# Remote.net
KiCad netlist of a schematic drawn in EAGLE
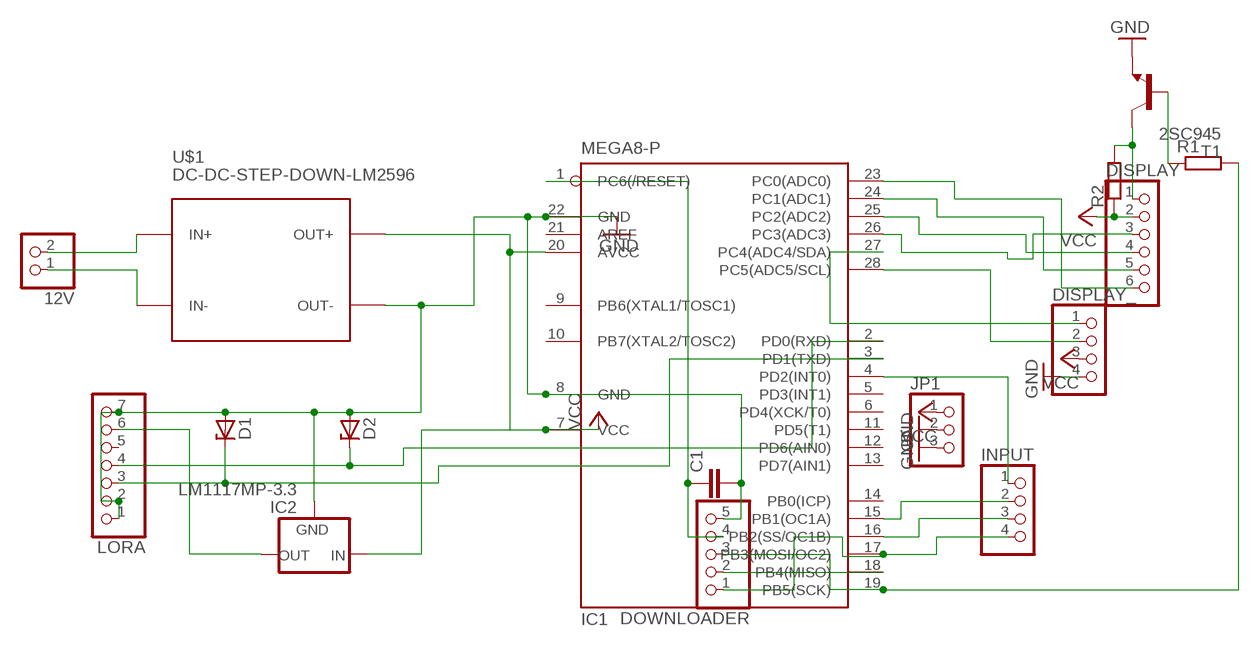
[diagram p0: schematic, sheet 1]

(export (version "E")
  (design (tool "Eeschema 10.0.6"))
  (components
    (comp (ref "12V")
      (value "PINHD-1X2")
      (footprint "eagle-import:1X02")
      (libsource (lib "eagle-import") (part "PINHD-1X2"))
    )
    (comp (ref "C1")
      (value "C-EU025-024X044")
      (footprint "eagle-import:C025-024X044")
      (libsource (lib "eagle-import") (part "C-EU025-024X044"))
    )
    (comp (ref "D1")
      (value "ZENER-DIODEDO35Z10")
      (footprint "eagle-import:DO35Z10")
      (libsource (lib "eagle-import") (part "ZENER-DIODEDO35Z10"))
    )
    (comp (ref "D2")
      (value "ZENER-DIODEDO35Z10")
      (footprint "eagle-import:DO35Z10")
      (libsource (lib "eagle-import") (part "ZENER-DIODEDO35Z10"))
    )
    (comp (ref "DISPLAY")
      (value "PINHD-1X6")
      (footprint "eagle-import:1X06")
      (libsource (lib "eagle-import") (part "PINHD-1X6"))
    )
    (comp (ref "DISPLAY_")
      (value "PINHD-1X4")
      (footprint "eagle-import:1X04")
      (libsource (lib "eagle-import") (part "PINHD-1X4"))
    )
    (comp (ref "DOWNLOADER")
      (value "PINHD-1X5")
      (footprint "eagle-import:1X05")
      (libsource (lib "eagle-import") (part "PINHD-1X5"))
    )
    (comp (ref "IC1")
      (value "MEGA8-P")
      (footprint "eagle-import:DIL28-3")
      (libsource (lib "eagle-import") (part "MEGA8-P"))
    )
    (comp (ref "IC2")
      (value "LM1117MP-3.3")
      (footprint "eagle-import:SOT223")
      (fields (field (name "MF") "Texas Instruments"))
      (libsource (lib "eagle-import") (part "LM1117?-MP3.3"))
    )
    (comp (ref "INPUT")
      (value "PINHD-1X4")
      (footprint "eagle-import:1X04")
      (libsource (lib "eagle-import") (part "PINHD-1X4"))
    )
    (comp (ref "JP1")
      (value "PINHD-1X3")
      (footprint "eagle-import:1X03")
      (libsource (lib "eagle-import") (part "PINHD-1X3"))
    )
    (comp (ref "LORA")
      (value "PINHD-1X7")
      (footprint "eagle-import:1X07")
      (libsource (lib "eagle-import") (part "PINHD-1X7"))
    )
    (comp (ref "R1")
      (value "R-EU_0204/7")
      (footprint "eagle-import:0204_7")
      (libsource (lib "eagle-import") (part "R-EU_0204/7"))
    )
    (comp (ref "R2")
      (value "R-EU_0204/7")
      (footprint "eagle-import:0204_7")
      (libsource (lib "eagle-import") (part "R-EU_0204/7"))
    )
    (comp (ref "T1")
      (value "2SC945")
      (footprint "eagle-import:TO92-ECB")
      (libsource (lib "eagle-import") (part "2SC945"))
    )
    (comp (ref "U$1")
      (value "DC-DC-STEP-DOWN-LM2596")
      (footprint "eagle-import:DC-DC-STEP-DOWN-LM2596")
      (libsource (lib "eagle-import") (part "DC-DC-STEP-DOWN-LM2596"))
    )
  )
  (nets
    (net (code "1") (name "GND") (class "Default")
      (node (ref "C1") (pin "2") (pinfunction "2_2") (pintype "passive"))
      (node (ref "D1") (pin "A") (pinfunction "A_A") (pintype "passive"))
      (node (ref "D2") (pin "A") (pinfunction "A_A") (pintype "passive"))
      (node (ref "DISPLAY_") (pin "4") (pinfunction "4_4") (pintype "passive"))
      (node (ref "DOWNLOADER") (pin "5") (pinfunction "5_5") (pintype "passive"))
      (node (ref "IC1") (pin "22") (pinfunction "GND_22") (pintype "power_in"))
      (node (ref "IC1") (pin "8") (pinfunction "GND_8") (pintype "power_in"))
      (node (ref "IC2") (pin "1") (pinfunction "GND_1") (pintype "input"))
      (node (ref "JP1") (pin "2") (pinfunction "2_2") (pintype "passive"))
      (node (ref "JP1") (pin "3") (pinfunction "3_3") (pintype "passive"))
      (node (ref "LORA") (pin "1") (pinfunction "1_1") (pintype "passive"))
      (node (ref "LORA") (pin "2") (pinfunction "2_2") (pintype "passive"))
      (node (ref "LORA") (pin "7") (pinfunction "7_7") (pintype "passive"))
      (node (ref "T1") (pin "E") (pinfunction "E_E") (pintype "passive"))
      (node (ref "U$1") (pin "OUT-") (pinfunction "OUT-_OUT-") (pintype "bidirectional"))
    )
    (net (code "2") (name "Net-(12V-Pad1)") (class "Default")
      (node (ref "12V") (pin "1") (pinfunction "1_1") (pintype "passive"))
      (node (ref "U$1") (pin "IN-") (pinfunction "IN-_IN-") (pintype "bidirectional"))
    )
    (net (code "3") (name "Net-(12V-Pad2)") (class "Default")
      (node (ref "12V") (pin "2") (pinfunction "2_2") (pintype "passive"))
      (node (ref "U$1") (pin "IN+") (pinfunction "IN+_IN+") (pintype "bidirectional"))
    )
    (net (code "4") (name "Net-(DISPLAY-Pad1)") (class "Default")
      (node (ref "DISPLAY") (pin "1") (pinfunction "1_1") (pintype "passive"))
      (node (ref "R2") (pin "2") (pinfunction "2_2") (pintype "passive"))
      (node (ref "T1") (pin "C") (pinfunction "C_C") (pintype "passive"))
    )
    (net (code "5") (name "Net-(IC1-PB1(OC1A))") (class "Default")
      (node (ref "IC1") (pin "15") (pinfunction "PB1(OC1A)_15") (pintype "bidirectional"))
      (node (ref "INPUT") (pin "2") (pinfunction "2_2") (pintype "passive"))
    )
    (net (code "6") (name "Net-(IC1-PB2(SS{slash}OC1B))") (class "Default")
      (node (ref "IC1") (pin "16") (pinfunction "PB2(SS/OC1B)_16") (pintype "bidirectional"))
      (node (ref "INPUT") (pin "3") (pinfunction "3_3") (pintype "passive"))
    )
    (net (code "7") (name "Net-(IC1-PB3(MOSI{slash}OC2))") (class "Default")
      (node (ref "DOWNLOADER") (pin "1") (pinfunction "1_1") (pintype "passive"))
      (node (ref "IC1") (pin "17") (pinfunction "PB3(MOSI/OC2)_17") (pintype "bidirectional"))
      (node (ref "INPUT") (pin "4") (pinfunction "4_4") (pintype "passive"))
    )
    (net (code "8") (name "Net-(IC1-PB4(MISO))") (class "Default")
      (node (ref "DOWNLOADER") (pin "2") (pinfunction "2_2") (pintype "passive"))
      (node (ref "IC1") (pin "18") (pinfunction "PB4(MISO)_18") (pintype "bidirectional"))
    )
    (net (code "9") (name "Net-(IC1-PB5(SCK))") (class "Default")
      (node (ref "DOWNLOADER") (pin "3") (pinfunction "3_3") (pintype "passive"))
      (node (ref "IC1") (pin "19") (pinfunction "PB5(SCK)_19") (pintype "bidirectional"))
      (node (ref "R1") (pin "2") (pinfunction "2_2") (pintype "passive"))
    )
    (net (code "10") (name "Net-(IC1-PC0(ADC0))") (class "Default")
      (node (ref "DISPLAY") (pin "6") (pinfunction "6_6") (pintype "passive"))
      (node (ref "IC1") (pin "23") (pinfunction "PC0(ADC0)_23") (pintype "bidirectional"))
    )
    (net (code "11") (name "Net-(IC1-PC1(ADC1))") (class "Default")
      (node (ref "DISPLAY") (pin "5") (pinfunction "5_5") (pintype "passive"))
      (node (ref "IC1") (pin "24") (pinfunction "PC1(ADC1)_24") (pintype "bidirectional"))
    )
    (net (code "12") (name "Net-(IC1-PC2(ADC2))") (class "Default")
      (node (ref "DISPLAY") (pin "4") (pinfunction "4_4") (pintype "passive"))
      (node (ref "IC1") (pin "25") (pinfunction "PC2(ADC2)_25") (pintype "bidirectional"))
    )
    (net (code "13") (name "Net-(IC1-PC3(ADC3))") (class "Default")
      (node (ref "DISPLAY") (pin "3") (pinfunction "3_3") (pintype "passive"))
      (node (ref "IC1") (pin "26") (pinfunction "PC3(ADC3)_26") (pintype "bidirectional"))
    )
    (net (code "14") (name "Net-(IC1-PC4(ADC4{slash}SDA))") (class "Default")
      (node (ref "DISPLAY_") (pin "1") (pinfunction "1_1") (pintype "passive"))
      (node (ref "IC1") (pin "27") (pinfunction "PC4(ADC4/SDA)_27") (pintype "bidirectional"))
    )
    (net (code "15") (name "Net-(IC1-PC5(ADC5{slash}SCL))") (class "Default")
      (node (ref "DISPLAY_") (pin "2") (pinfunction "2_2") (pintype "passive"))
      (node (ref "IC1") (pin "28") (pinfunction "PC5(ADC5/SCL)_28") (pintype "bidirectional"))
    )
    (net (code "16") (name "Net-(IC1-PC6({slash}RESET))") (class "Default")
      (node (ref "C1") (pin "1") (pinfunction "1_1") (pintype "passive"))
      (node (ref "DOWNLOADER") (pin "4") (pinfunction "4_4") (pintype "passive"))
      (node (ref "IC1") (pin "1") (pinfunction "PC6(/RESET)_1") (pintype "bidirectional"))
    )
    (net (code "17") (name "Net-(IC1-PD0(RXD))") (class "Default")
      (node (ref "D2") (pin "C") (pinfunction "C_C") (pintype "passive"))
      (node (ref "IC1") (pin "2") (pinfunction "PD0(RXD)_2") (pintype "bidirectional"))
      (node (ref "LORA") (pin "4") (pinfunction "4_4") (pintype "passive"))
    )
    (net (code "18") (name "Net-(IC1-PD1(TXD))") (class "Default")
      (node (ref "D1") (pin "C") (pinfunction "C_C") (pintype "passive"))
      (node (ref "IC1") (pin "3") (pinfunction "PD1(TXD)_3") (pintype "bidirectional"))
      (node (ref "LORA") (pin "3") (pinfunction "3_3") (pintype "passive"))
    )
    (net (code "19") (name "Net-(IC1-PD2(INT0))") (class "Default")
      (node (ref "IC1") (pin "4") (pinfunction "PD2(INT0)_4") (pintype "bidirectional"))
      (node (ref "INPUT") (pin "1") (pinfunction "1_1") (pintype "passive"))
    )
    (net (code "20") (name "Net-(IC2-OUT-Pad2)") (class "Default")
      (node (ref "IC2") (pin "2") (pinfunction "OUT_2") (pintype "passive"))
      (node (ref "IC2") (pin "4") (pinfunction "OUT_4") (pintype "passive"))
      (node (ref "LORA") (pin "6") (pinfunction "6_6") (pintype "passive"))
    )
    (net (code "21") (name "Net-(R1-Pad1)") (class "Default")
      (node (ref "R1") (pin "1") (pinfunction "1_1") (pintype "passive"))
      (node (ref "T1") (pin "B") (pinfunction "B_B") (pintype "passive"))
    )
    (net (code "22") (name "VCC") (class "Default")
      (node (ref "DISPLAY") (pin "2") (pinfunction "2_2") (pintype "passive"))
      (node (ref "DISPLAY_") (pin "3") (pinfunction "3_3") (pintype "passive"))
      (node (ref "IC1") (pin "20") (pinfunction "AVCC_20") (pintype "power_in"))
      (node (ref "IC1") (pin "7") (pinfunction "VCC_7") (pintype "power_in"))
      (node (ref "IC2") (pin "3") (pinfunction "IN_3") (pintype "input"))
      (node (ref "JP1") (pin "1") (pinfunction "1_1") (pintype "passive"))
      (node (ref "R2") (pin "1") (pinfunction "1_1") (pintype "passive"))
      (node (ref "U$1") (pin "OUT+") (pinfunction "OUT+_OUT+") (pintype "bidirectional"))
    )
    (net (code "23") (name "unconnected-(IC1-AREF-Pad21)") (class "Default")
      (node (ref "IC1") (pin "21") (pinfunction "AREF_21") (pintype "passive"))
    )
    (net (code "24") (name "unconnected-(IC1-PB0(ICP)-Pad14)") (class "Default")
      (node (ref "IC1") (pin "14") (pinfunction "PB0(ICP)_14") (pintype "bidirectional"))
    )
    (net (code "25") (name "unconnected-(IC1-PB6(XTAL1{slash}TOSC1)-Pad9)") (class "Default")
      (node (ref "IC1") (pin "9") (pinfunction "PB6(XTAL1/TOSC1)_9") (pintype "bidirectional"))
    )
    (net (code "26") (name "unconnected-(IC1-PB7(XTAL2{slash}TOSC2)-Pad10)") (class "Default")
      (node (ref "IC1") (pin "10") (pinfunction "PB7(XTAL2/TOSC2)_10") (pintype "bidirectional"))
    )
    (net (code "27") (name "unconnected-(IC1-PD3(INT1)-Pad5)") (class "Default")
      (node (ref "IC1") (pin "5") (pinfunction "PD3(INT1)_5") (pintype "bidirectional"))
    )
    (net (code "28") (name "unconnected-(IC1-PD4(XCK{slash}T0)-Pad6)") (class "Default")
      (node (ref "IC1") (pin "6") (pinfunction "PD4(XCK/T0)_6") (pintype "bidirectional"))
    )
    (net (code "29") (name "unconnected-(IC1-PD5(T1)-Pad11)") (class "Default")
      (node (ref "IC1") (pin "11") (pinfunction "PD5(T1)_11") (pintype "bidirectional"))
    )
    (net (code "30") (name "unconnected-(IC1-PD6(AIN0)-Pad12)") (class "Default")
      (node (ref "IC1") (pin "12") (pinfunction "PD6(AIN0)_12") (pintype "bidirectional"))
    )
    (net (code "31") (name "unconnected-(IC1-PD7(AIN1)-Pad13)") (class "Default")
      (node (ref "IC1") (pin "13") (pinfunction "PD7(AIN1)_13") (pintype "bidirectional"))
    )
    (net (code "32") (name "unconnected-(LORA-Pad5)") (class "Default")
      (node (ref "LORA") (pin "5") (pinfunction "5_5") (pintype "passive"))
    )
  )
)
